# USB.net
KiCad netlist of a schematic drawn in Altium Designer
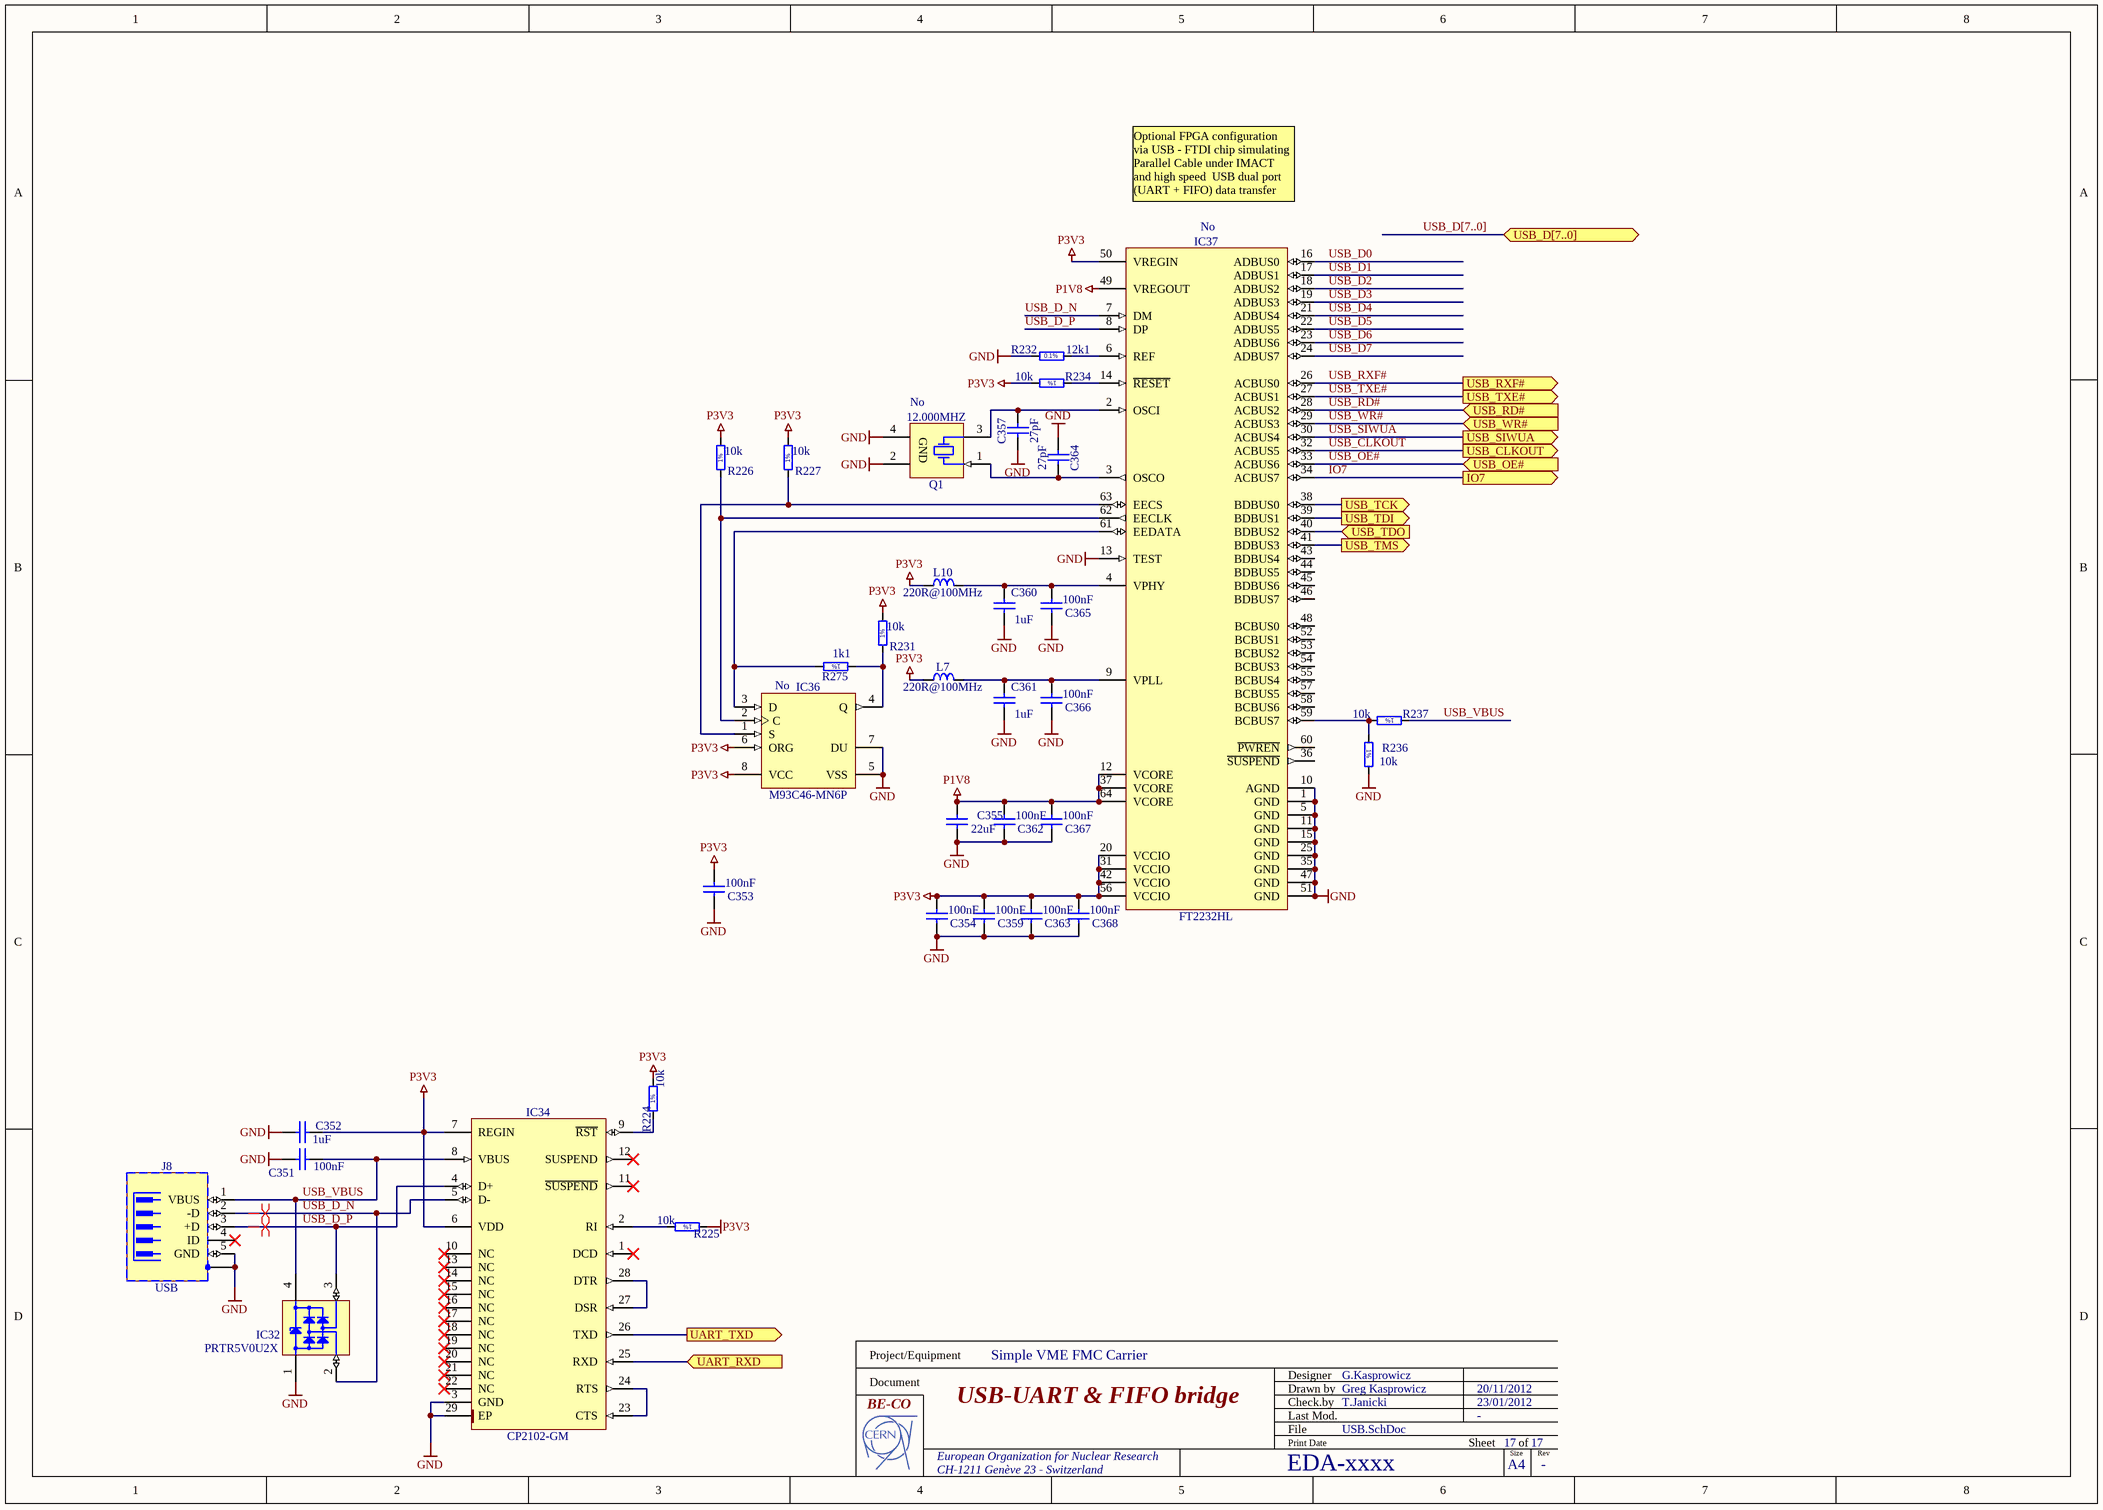
[diagram p0: USB.SchDoc]

(export (version "E")
  (design (tool "Eeschema 10.0.6"))
  (components
    (comp (ref "C351")
      (value "100nF")
      (footprint "CAPC1005X55N")
      (description "Non-polarised capacitor")
      (fields
        (field (name "PART NUMBER") "CC0402_100NF_16V_10%_X7R")
        (field (name "VOLTAGE") "16V")
        (field (name "AUTHOR") "CERN DEM JLC")
      )
      (libsource (lib "Capacitors") (part "Capacitor - non polarized"))
    )
    (comp (ref "C352")
      (value "1uF")
      (footprint "CAPC1608X87N")
      (description "Non-polarised capacitor")
      (fields
        (field (name "PART NUMBER") "CC0603_1UF_16V_10%_X7R")
        (field (name "VOLTAGE") "16V")
        (field (name "AUTHOR") "CERN DEM JLC")
      )
      (libsource (lib "Capacitors") (part "Capacitor - non polarized"))
    )
    (comp (ref "C353")
      (value "100nF")
      (footprint "CAPC1005X55N")
      (description "Non-polarised capacitor")
      (fields
        (field (name "PART NUMBER") "CC0402_100NF_16V_10%_X7R")
        (field (name "VOLTAGE") "16V")
        (field (name "AUTHOR") "CERN DEM JLC")
      )
      (libsource (lib "Capacitors") (part "Capacitor - non polarized"))
    )
    (comp (ref "C354")
      (value "100nF")
      (footprint "CAPC1005X55N")
      (description "Non-polarised capacitor")
      (fields
        (field (name "PART NUMBER") "CC0402_100NF_16V_10%_X7R")
        (field (name "VOLTAGE") "16V")
        (field (name "AUTHOR") "CERN DEM JLC")
      )
      (libsource (lib "Capacitors") (part "Capacitor - non polarized"))
    )
    (comp (ref "C355")
      (value "22uF")
      (footprint "CAPC3216X180N")
      (description "Non-polarised capacitor")
      (fields
        (field (name "PART NUMBER") "CC1206_22UF_10V_10%_X7R")
        (field (name "VOLTAGE") "10V")
        (field (name "AUTHOR") "CERN DEM JLC")
      )
      (libsource (lib "Capacitors") (part "Capacitor - non polarized"))
    )
    (comp (ref "C357")
      (value "27pF")
      (footprint "CAPC1608X87N")
      (description "Non-polarised capacitor")
      (fields
        (field (name "PART NUMBER") "CC0603_27PF_50V_5%_NP0")
        (field (name "VOLTAGE") "50V")
        (field (name "AUTHOR") "CERN DEM JLC")
      )
      (libsource (lib "Capacitors") (part "Capacitor - non polarized"))
    )
    (comp (ref "C359")
      (value "100nF")
      (footprint "CAPC1005X55N")
      (description "Non-polarised capacitor")
      (fields
        (field (name "PART NUMBER") "CC0402_100NF_16V_10%_X7R")
        (field (name "VOLTAGE") "16V")
        (field (name "AUTHOR") "CERN DEM JLC")
      )
      (libsource (lib "Capacitors") (part "Capacitor - non polarized"))
    )
    (comp (ref "C360")
      (value "1uF")
      (footprint "CAPC1608X87N")
      (description "Non-polarised capacitor")
      (fields
        (field (name "PART NUMBER") "CC0603_1UF_16V_10%_X7R")
        (field (name "VOLTAGE") "16V")
        (field (name "AUTHOR") "CERN DEM JLC")
      )
      (libsource (lib "Capacitors") (part "Capacitor - non polarized"))
    )
    (comp (ref "C361")
      (value "1uF")
      (footprint "CAPC1608X87N")
      (description "Non-polarised capacitor")
      (fields
        (field (name "PART NUMBER") "CC0603_1UF_16V_10%_X7R")
        (field (name "VOLTAGE") "16V")
        (field (name "AUTHOR") "CERN DEM JLC")
      )
      (libsource (lib "Capacitors") (part "Capacitor - non polarized"))
    )
    (comp (ref "C362")
      (value "100nF")
      (footprint "CAPC1005X55N")
      (description "Non-polarised capacitor")
      (fields
        (field (name "PART NUMBER") "CC0402_100NF_16V_10%_X7R")
        (field (name "VOLTAGE") "16V")
        (field (name "AUTHOR") "CERN DEM JLC")
      )
      (libsource (lib "Capacitors") (part "Capacitor - non polarized"))
    )
    (comp (ref "C363")
      (value "100nF")
      (footprint "CAPC1005X55N")
      (description "Non-polarised capacitor")
      (fields
        (field (name "PART NUMBER") "CC0402_100NF_16V_10%_X7R")
        (field (name "VOLTAGE") "16V")
        (field (name "AUTHOR") "CERN DEM JLC")
      )
      (libsource (lib "Capacitors") (part "Capacitor - non polarized"))
    )
    (comp (ref "C364")
      (value "27pF")
      (footprint "CAPC1608X87N")
      (description "Non-polarised capacitor")
      (fields
        (field (name "PART NUMBER") "CC0603_27PF_50V_5%_NP0")
        (field (name "VOLTAGE") "50V")
        (field (name "AUTHOR") "CERN DEM JLC")
      )
      (libsource (lib "Capacitors") (part "Capacitor - non polarized"))
    )
    (comp (ref "C365")
      (value "100nF")
      (footprint "CAPC1005X55N")
      (description "Non-polarised capacitor")
      (fields
        (field (name "PART NUMBER") "CC0402_100NF_16V_10%_X7R")
        (field (name "VOLTAGE") "16V")
        (field (name "AUTHOR") "CERN DEM JLC")
      )
      (libsource (lib "Capacitors") (part "Capacitor - non polarized"))
    )
    (comp (ref "C366")
      (value "100nF")
      (footprint "CAPC1005X55N")
      (description "Non-polarised capacitor")
      (fields
        (field (name "PART NUMBER") "CC0402_100NF_16V_10%_X7R")
        (field (name "VOLTAGE") "16V")
        (field (name "AUTHOR") "CERN DEM JLC")
      )
      (libsource (lib "Capacitors") (part "Capacitor - non polarized"))
    )
    (comp (ref "C367")
      (value "100nF")
      (footprint "CAPC1005X55N")
      (description "Non-polarised capacitor")
      (fields
        (field (name "PART NUMBER") "CC0402_100NF_16V_10%_X7R")
        (field (name "VOLTAGE") "16V")
        (field (name "AUTHOR") "CERN DEM JLC")
      )
      (libsource (lib "Capacitors") (part "Capacitor - non polarized"))
    )
    (comp (ref "C368")
      (value "100nF")
      (footprint "CAPC1005X55N")
      (description "Non-polarised capacitor")
      (fields
        (field (name "PART NUMBER") "CC0402_100NF_16V_10%_X7R")
        (field (name "VOLTAGE") "16V")
        (field (name "AUTHOR") "CERN DEM JLC")
      )
      (libsource (lib "Capacitors") (part "Capacitor - non polarized"))
    )
    (comp (ref "IC32")
      (value "PRTR5V0U2X")
      (footprint "SOT190P230X110-4N")
      (description "Ultra Low Capacitance Double Rail-to-Rail ESD Protection Diode")
      (fields
        (field (name "VOLTAGE") "5.5V")
        (field (name "MANUFACTURER") "PHILIPS NXP")
        (field (name "AUTHOR") "CERN DEM JLC")
      )
      (libsource (lib "ICs And Semiconductors") (part "PRTR5V0U2X"))
    )
    (comp (ref "IC34")
      (value "CP2102-GM")
      (footprint "QFN50P500X500X100-29N-S335")
      (description "Single-Chip USB to UART Bridge")
      (fields (field (name "MANUFACTURER") "SILICON LABS") (field (name "AUTHOR") "CERN DEM JLC"))
      (libsource (lib "ICs And Semiconductors") (part "CP2102-GM"))
    )
    (comp (ref "IC36")
      (value "M93C46-MN6P")
      (footprint "SOIC127P600X175-8N")
      (description "1Kb (x8/x16) Serial Microwire Bus EEPROM")
      (fields
        (field (name "MANUFACTURER") "ST MICROELECTRONICS")
        (field (name "MOUNTED") "No")
        (field (name "AUTHOR") "CERN DEM JLC")
      )
      (libsource (lib "ICs And Semiconductors") (part "M93C46-MN"))
    )
    (comp (ref "IC37")
      (value "FT2232HL")
      (footprint "QFP50P1200X1200X160-64N")
      (description "Dual High Speed USB to Multipurpose UART/FIFO IC")
      (fields
        (field (name "MANUFACTURER") "FUTURE TECHNOLOGY DEVICES INTERNATIONAL (FTDI)")
        (field (name "MOUNTED") "No")
        (field (name "AUTHOR") "CERN DEM JLC")
      )
      (libsource (lib "ICs And Semiconductors") (part "FT2232H"))
    )
    (comp (ref "J8")
      (value "USB")
      (footprint "TYCO_1734035-1")
      (description "5 Pin + 1 Shield USB Receptacle")
      (fields
        (field (name "PART NUMBER") "TYCO_1734035-1")
        (field (name "MANUFACTURER") "TYCO ELECTRONICS")
        (field (name "AUTHOR") "CERN DEM JLC")
      )
      (libsource (lib "Connectors") (part "Connector USB 5 Pin + 1Shield"))
    )
    (comp (ref "L7")
      (value "220R@100MHz")
      (footprint "INDC2012X105N")
      (description "Inductor")
      (fields
        (field (name "PART NUMBER") "IND0805_MURATA_BLM21PG221SN1D")
        (field (name "POWER") "2A")
        (field (name "AUTHOR") "CERN DEM JLC")
      )
      (libsource (lib "Inductors & Transformers") (part "Inductor"))
    )
    (comp (ref "L10")
      (value "220R@100MHz")
      (footprint "INDC2012X105N")
      (description "Inductor")
      (fields
        (field (name "PART NUMBER") "IND0805_MURATA_BLM21PG221SN1D")
        (field (name "POWER") "2A")
        (field (name "AUTHOR") "CERN DEM JLC")
      )
      (libsource (lib "Inductors & Transformers") (part "Inductor"))
    )
    (comp (ref "Q1")
      (value "12.000MHZ")
      (footprint "XTAL_ABRACON_ABM3B")
      (description "Crystal 4 pins 1=XTAL Control 2=GND3=XTAL 4=GND")
      (fields
        (field (name "PART NUMBER") "XTAL_12.000MHZ_ABRACON_ABM3B-12.000MHZ-B2-T")
        (field (name "MANUFACTURER") "ABRACON")
        (field (name "MOUNTED") "No")
        (field (name "AUTHOR") "CERN DEM JLC")
      )
      (libsource (lib "ICs And Semiconductors") (part "Quartz Crystal 1X 2GND 3X 4GND"))
    )
    (comp (ref "R224")
      (value "10k")
      (footprint "RESC1608X55N")
      (description "Resistor - 1%")
      (fields
        (field (name "PART NUMBER") "R0603_10K_1%_0.1W_100PPM")
        (field (name "POWER") "0.1W")
        (field (name "AUTHOR") "CERN DEM JLC")
      )
      (libsource (lib "Resistors") (part "Resistor - 1%"))
    )
    (comp (ref "R225")
      (value "10k")
      (footprint "RESC1608X55N")
      (description "Resistor - 1%")
      (fields
        (field (name "PART NUMBER") "R0603_10K_1%_0.1W_100PPM")
        (field (name "POWER") "0.1W")
        (field (name "AUTHOR") "CERN DEM JLC")
      )
      (libsource (lib "Resistors") (part "Resistor - 1%"))
    )
    (comp (ref "R226")
      (value "10k")
      (footprint "RESC1608X55N")
      (description "Resistor - 1%")
      (fields
        (field (name "PART NUMBER") "R0603_10K_1%_0.1W_100PPM")
        (field (name "POWER") "0.1W")
        (field (name "AUTHOR") "CERN DEM JLC")
      )
      (libsource (lib "Resistors") (part "Resistor - 1%"))
    )
    (comp (ref "R227")
      (value "10k")
      (footprint "RESC1608X55N")
      (description "Resistor - 1%")
      (fields
        (field (name "PART NUMBER") "R0603_10K_1%_0.1W_100PPM")
        (field (name "POWER") "0.1W")
        (field (name "AUTHOR") "CERN DEM JLC")
      )
      (libsource (lib "Resistors") (part "Resistor - 1%"))
    )
    (comp (ref "R231")
      (value "10k")
      (footprint "RESC1608X55N")
      (description "Resistor - 1%")
      (fields
        (field (name "PART NUMBER") "R0603_10K_1%_0.1W_100PPM")
        (field (name "POWER") "0.1W")
        (field (name "AUTHOR") "CERN DEM JLC")
      )
      (libsource (lib "Resistors") (part "Resistor - 1%"))
    )
    (comp (ref "R232")
      (value "12k1")
      (footprint "RESC1608X55N")
      (description "Resistor - 0.1%")
      (fields
        (field (name "PART NUMBER") "R0603_12K1_0.1%_0.063W_10PPM")
        (field (name "POWER") "0.063W")
        (field (name "AUTHOR") "CERN DEM JLC")
      )
      (libsource (lib "Resistors") (part "Resistor - 0.1%"))
    )
    (comp (ref "R234")
      (value "10k")
      (footprint "RESC1608X55N")
      (description "Resistor - 1%")
      (fields
        (field (name "PART NUMBER") "R0603_10K_1%_0.1W_100PPM")
        (field (name "POWER") "0.1W")
        (field (name "AUTHOR") "CERN DEM JLC")
      )
      (libsource (lib "Resistors") (part "Resistor - 1%"))
    )
    (comp (ref "R236")
      (value "10k")
      (footprint "RESC1608X55N")
      (description "Resistor - 1%")
      (fields
        (field (name "PART NUMBER") "R0603_10K_1%_0.1W_100PPM")
        (field (name "POWER") "0.1W")
        (field (name "AUTHOR") "CERN DEM JLC")
      )
      (libsource (lib "Resistors") (part "Resistor - 1%"))
    )
    (comp (ref "R237")
      (value "10k")
      (footprint "RESC1608X55N")
      (description "Resistor - 1%")
      (fields
        (field (name "PART NUMBER") "R0603_10K_1%_0.1W_100PPM")
        (field (name "POWER") "0.1W")
        (field (name "AUTHOR") "CERN DEM JLC")
      )
      (libsource (lib "Resistors") (part "Resistor - 1%"))
    )
    (comp (ref "R275")
      (value "1k1")
      (footprint "RESC1608X55N")
      (description "Resistor - 1%")
      (fields
        (field (name "PART NUMBER") "R0603_1K1_1%_0.1W_100PPM")
        (field (name "POWER") "0.1W")
        (field (name "AUTHOR") "CERN DEM JLC")
      )
      (libsource (lib "Resistors") (part "Resistor - 1%"))
    )
  )
  (nets
    (net (code "1") (name "/IO7") (class "Default")
      (node (ref "IC37") (pin "34") (pinfunction "ACBUS7_34") (pintype "bidirectional"))
    )
    (net (code "2") (name "/UART_RXD") (class "Default")
      (node (ref "IC34") (pin "25") (pinfunction "RXD_25") (pintype "input"))
    )
    (net (code "3") (name "/UART_TXD") (class "Default")
      (node (ref "IC34") (pin "26") (pinfunction "TXD_26") (pintype "output"))
    )
    (net (code "4") (name "/USB_CLKOUT") (class "Default")
      (node (ref "IC37") (pin "32") (pinfunction "ACBUS5_32") (pintype "bidirectional"))
    )
    (net (code "5") (name "/USB_D0") (class "Default")
      (node (ref "IC37") (pin "16") (pinfunction "ADBUS0_16") (pintype "bidirectional"))
    )
    (net (code "6") (name "/USB_D1") (class "Default")
      (node (ref "IC37") (pin "17") (pinfunction "ADBUS1_17") (pintype "bidirectional"))
    )
    (net (code "7") (name "/USB_D2") (class "Default")
      (node (ref "IC37") (pin "18") (pinfunction "ADBUS2_18") (pintype "bidirectional"))
    )
    (net (code "8") (name "/USB_D3") (class "Default")
      (node (ref "IC37") (pin "19") (pinfunction "ADBUS3_19") (pintype "bidirectional"))
    )
    (net (code "9") (name "/USB_D4") (class "Default")
      (node (ref "IC37") (pin "21") (pinfunction "ADBUS4_21") (pintype "bidirectional"))
    )
    (net (code "10") (name "/USB_D5") (class "Default")
      (node (ref "IC37") (pin "22") (pinfunction "ADBUS5_22") (pintype "bidirectional"))
    )
    (net (code "11") (name "/USB_D6") (class "Default")
      (node (ref "IC37") (pin "23") (pinfunction "ADBUS6_23") (pintype "bidirectional"))
    )
    (net (code "12") (name "/USB_D7") (class "Default")
      (node (ref "IC37") (pin "24") (pinfunction "ADBUS7_24") (pintype "bidirectional"))
    )
    (net (code "14") (name "/USB_D_N") (class "Default")
      (node (ref "IC32") (pin "2") (pinfunction "I/O1_2") (pintype "bidirectional"))
      (node (ref "IC34") (pin "5") (pinfunction "D-_5") (pintype "bidirectional"))
      (node (ref "IC37") (pin "7") (pinfunction "DM_7") (pintype "input"))
      (node (ref "J8") (pin "2") (pinfunction "-D_2") (pintype "bidirectional"))
    )
    (net (code "15") (name "/USB_D_P") (class "Default")
      (node (ref "IC32") (pin "3") (pinfunction "I/O2_3") (pintype "bidirectional"))
      (node (ref "IC34") (pin "4") (pinfunction "D+_4") (pintype "bidirectional"))
      (node (ref "IC37") (pin "8") (pinfunction "DP_8") (pintype "input"))
      (node (ref "J8") (pin "3") (pinfunction "+D_3") (pintype "bidirectional"))
    )
    (net (code "16") (name "/USB_OE#") (class "Default")
      (node (ref "IC37") (pin "33") (pinfunction "ACBUS6_33") (pintype "bidirectional"))
    )
    (net (code "17") (name "/USB_RD#") (class "Default")
      (node (ref "IC37") (pin "28") (pinfunction "ACBUS2_28") (pintype "bidirectional"))
    )
    (net (code "18") (name "/USB_RXF#") (class "Default")
      (node (ref "IC37") (pin "26") (pinfunction "ACBUS0_26") (pintype "bidirectional"))
    )
    (net (code "19") (name "/USB_SIWUA") (class "Default")
      (node (ref "IC37") (pin "30") (pinfunction "ACBUS4_30") (pintype "bidirectional"))
    )
    (net (code "20") (name "/USB_TCK") (class "Default")
      (node (ref "IC37") (pin "38") (pinfunction "BDBUS0_38") (pintype "bidirectional"))
    )
    (net (code "21") (name "/USB_TDI") (class "Default")
      (node (ref "IC37") (pin "39") (pinfunction "BDBUS1_39") (pintype "bidirectional"))
    )
    (net (code "22") (name "/USB_TDO") (class "Default")
      (node (ref "IC37") (pin "40") (pinfunction "BDBUS2_40") (pintype "bidirectional"))
    )
    (net (code "23") (name "/USB_TMS") (class "Default")
      (node (ref "IC37") (pin "41") (pinfunction "BDBUS3_41") (pintype "bidirectional"))
    )
    (net (code "24") (name "/USB_TXE#") (class "Default")
      (node (ref "IC37") (pin "27") (pinfunction "ACBUS1_27") (pintype "bidirectional"))
    )
    (net (code "25") (name "/USB_VBUS") (class "Default")
      (node (ref "C351") (pin "1") (pinfunction "1_1") (pintype "passive"))
      (node (ref "IC32") (pin "4") (pinfunction "VCC_4") (pintype "power_in"))
      (node (ref "IC34") (pin "8") (pinfunction "VBUS_8") (pintype "input"))
      (node (ref "J8") (pin "1") (pinfunction "VBUS_1") (pintype "bidirectional"))
      (node (ref "R237") (pin "1") (pinfunction "1_1") (pintype "passive"))
    )
    (net (code "26") (name "/USB_WR#") (class "Default")
      (node (ref "IC37") (pin "29") (pinfunction "ACBUS3_29") (pintype "bidirectional"))
    )
    (net (code "27") (name "GND") (class "Default")
      (node (ref "C351") (pin "2") (pinfunction "2_2") (pintype "passive"))
      (node (ref "C352") (pin "2") (pinfunction "2_2") (pintype "passive"))
      (node (ref "C353") (pin "2") (pinfunction "2_2") (pintype "passive"))
      (node (ref "C354") (pin "2") (pinfunction "2_2") (pintype "passive"))
      (node (ref "C355") (pin "1") (pinfunction "1_1") (pintype "passive"))
      (node (ref "C357") (pin "1") (pinfunction "1_1") (pintype "passive"))
      (node (ref "C359") (pin "2") (pinfunction "2_2") (pintype "passive"))
      (node (ref "C360") (pin "1") (pinfunction "1_1") (pintype "passive"))
      (node (ref "C361") (pin "1") (pinfunction "1_1") (pintype "passive"))
      (node (ref "C362") (pin "2") (pinfunction "2_2") (pintype "passive"))
      (node (ref "C363") (pin "2") (pinfunction "2_2") (pintype "passive"))
      (node (ref "C364") (pin "1") (pinfunction "1_1") (pintype "passive"))
      (node (ref "C365") (pin "2") (pinfunction "2_2") (pintype "passive"))
      (node (ref "C366") (pin "2") (pinfunction "2_2") (pintype "passive"))
      (node (ref "C367") (pin "2") (pinfunction "2_2") (pintype "passive"))
      (node (ref "C368") (pin "2") (pinfunction "2_2") (pintype "passive"))
      (node (ref "IC32") (pin "1") (pinfunction "GND_1") (pintype "power_in"))
      (node (ref "IC34") (pin "29") (pinfunction "EP_29") (pintype "power_in"))
      (node (ref "IC34") (pin "3") (pinfunction "GND_3") (pintype "power_in"))
      (node (ref "IC36") (pin "5") (pinfunction "VSS_5") (pintype "power_in"))
      (node (ref "IC36") (pin "7") (pinfunction "DU_7") (pintype "passive"))
      (node (ref "IC37") (pin "1") (pinfunction "GND_1") (pintype "power_in"))
      (node (ref "IC37") (pin "10") (pinfunction "AGND_10") (pintype "power_in"))
      (node (ref "IC37") (pin "11") (pinfunction "GND_11") (pintype "power_in"))
      (node (ref "IC37") (pin "13") (pinfunction "TEST_13") (pintype "input"))
      (node (ref "IC37") (pin "15") (pinfunction "GND_15") (pintype "power_in"))
      (node (ref "IC37") (pin "25") (pinfunction "GND_25") (pintype "power_in"))
      (node (ref "IC37") (pin "35") (pinfunction "GND_35") (pintype "power_in"))
      (node (ref "IC37") (pin "47") (pinfunction "GND_47") (pintype "power_in"))
      (node (ref "IC37") (pin "5") (pinfunction "GND_5") (pintype "power_in"))
      (node (ref "IC37") (pin "51") (pinfunction "GND_51") (pintype "power_in"))
      (node (ref "J8") (pin "5") (pinfunction "GND_5") (pintype "bidirectional"))
      (node (ref "J8") (pin "6") (pinfunction "SH_6") (pintype "power_in"))
      (node (ref "Q1") (pin "2") (pinfunction "GND_2") (pintype "power_in"))
      (node (ref "Q1") (pin "4") (pinfunction "GND_4") (pintype "power_in"))
      (node (ref "R232") (pin "1") (pinfunction "1_1") (pintype "passive"))
      (node (ref "R236") (pin "2") (pinfunction "2_2") (pintype "passive"))
    )
    (net (code "28") (name "Net-(IC34-CTS)") (class "Default")
      (node (ref "IC34") (pin "23") (pinfunction "CTS_23") (pintype "input"))
      (node (ref "IC34") (pin "24") (pinfunction "RTS_24") (pintype "output"))
    )
    (net (code "29") (name "Net-(IC34-DSR)") (class "Default")
      (node (ref "IC34") (pin "27") (pinfunction "DSR_27") (pintype "input"))
      (node (ref "IC34") (pin "28") (pinfunction "DTR_28") (pintype "output"))
    )
    (net (code "30") (name "Net-(IC34-RI)") (class "Default")
      (node (ref "IC34") (pin "2") (pinfunction "RI_2") (pintype "input"))
      (node (ref "R225") (pin "2") (pinfunction "2_2") (pintype "passive"))
    )
    (net (code "31") (name "Net-(IC34-~{RST})") (class "Default")
      (node (ref "IC34") (pin "9") (pinfunction "~{RST}_9") (pintype "bidirectional"))
      (node (ref "R224") (pin "1") (pinfunction "1_1") (pintype "passive"))
    )
    (net (code "32") (name "Net-(IC36-C)") (class "Default")
      (node (ref "IC36") (pin "2") (pinfunction "C_2") (pintype "input"))
      (node (ref "IC37") (pin "62") (pinfunction "EECLK_62") (pintype "output"))
      (node (ref "R226") (pin "1") (pinfunction "1_1") (pintype "passive"))
    )
    (net (code "33") (name "Net-(IC36-D)") (class "Default")
      (node (ref "IC36") (pin "3") (pinfunction "D_3") (pintype "input"))
      (node (ref "IC37") (pin "61") (pinfunction "EEDATA_61") (pintype "bidirectional"))
      (node (ref "R275") (pin "2") (pinfunction "2_2") (pintype "passive"))
    )
    (net (code "34") (name "Net-(IC36-Q)") (class "Default")
      (node (ref "IC36") (pin "4") (pinfunction "Q_4") (pintype "output"))
      (node (ref "R231") (pin "1") (pinfunction "1_1") (pintype "passive"))
      (node (ref "R275") (pin "1") (pinfunction "1_1") (pintype "passive"))
    )
    (net (code "35") (name "Net-(IC36-S)") (class "Default")
      (node (ref "IC36") (pin "1") (pinfunction "S_1") (pintype "input"))
      (node (ref "IC37") (pin "63") (pinfunction "EECS_63") (pintype "bidirectional"))
      (node (ref "R227") (pin "1") (pinfunction "1_1") (pintype "passive"))
    )
    (net (code "36") (name "Net-(IC37-BCBUS7)") (class "Default")
      (node (ref "IC37") (pin "59") (pinfunction "BCBUS7_59") (pintype "bidirectional"))
      (node (ref "R236") (pin "1") (pinfunction "1_1") (pintype "passive"))
      (node (ref "R237") (pin "2") (pinfunction "2_2") (pintype "passive"))
    )
    (net (code "37") (name "Net-(IC37-OSCI)") (class "Default")
      (node (ref "C357") (pin "2") (pinfunction "2_2") (pintype "passive"))
      (node (ref "IC37") (pin "2") (pinfunction "OSCI_2") (pintype "input"))
      (node (ref "Q1") (pin "3") (pinfunction "X_3") (pintype "power_in"))
    )
    (net (code "38") (name "Net-(IC37-OSCO)") (class "Default")
      (node (ref "C364") (pin "2") (pinfunction "2_2") (pintype "passive"))
      (node (ref "IC37") (pin "3") (pinfunction "OSCO_3") (pintype "output"))
      (node (ref "Q1") (pin "1") (pinfunction "X_1") (pintype "input"))
    )
    (net (code "39") (name "Net-(IC37-REF)") (class "Default")
      (node (ref "IC37") (pin "6") (pinfunction "REF_6") (pintype "input"))
      (node (ref "R232") (pin "2") (pinfunction "2_2") (pintype "passive"))
    )
    (net (code "40") (name "Net-(IC37-VPHY)") (class "Default")
      (node (ref "C360") (pin "2") (pinfunction "2_2") (pintype "passive"))
      (node (ref "C365") (pin "1") (pinfunction "1_1") (pintype "passive"))
      (node (ref "IC37") (pin "4") (pinfunction "VPHY_4") (pintype "power_in"))
      (node (ref "L10") (pin "2") (pinfunction "2_2") (pintype "passive"))
    )
    (net (code "41") (name "Net-(IC37-VPLL)") (class "Default")
      (node (ref "C361") (pin "2") (pinfunction "2_2") (pintype "passive"))
      (node (ref "C366") (pin "1") (pinfunction "1_1") (pintype "passive"))
      (node (ref "IC37") (pin "9") (pinfunction "VPLL_9") (pintype "power_in"))
      (node (ref "L7") (pin "2") (pinfunction "2_2") (pintype "passive"))
    )
    (net (code "42") (name "Net-(IC37-~{RESET})") (class "Default")
      (node (ref "IC37") (pin "14") (pinfunction "~{RESET}_14") (pintype "input"))
      (node (ref "R234") (pin "1") (pinfunction "1_1") (pintype "passive"))
    )
    (net (code "43") (name "P1V8") (class "Default")
      (node (ref "C355") (pin "2") (pinfunction "2_2") (pintype "passive"))
      (node (ref "C362") (pin "1") (pinfunction "1_1") (pintype "passive"))
      (node (ref "C367") (pin "1") (pinfunction "1_1") (pintype "passive"))
      (node (ref "IC37") (pin "12") (pinfunction "VCORE_12") (pintype "power_in"))
      (node (ref "IC37") (pin "37") (pinfunction "VCORE_37") (pintype "power_in"))
      (node (ref "IC37") (pin "49") (pinfunction "VREGOUT_49") (pintype "power_in"))
      (node (ref "IC37") (pin "64") (pinfunction "VCORE_64") (pintype "power_in"))
    )
    (net (code "44") (name "P3V3") (class "Default")
      (node (ref "C352") (pin "1") (pinfunction "1_1") (pintype "passive"))
      (node (ref "C353") (pin "1") (pinfunction "1_1") (pintype "passive"))
      (node (ref "C354") (pin "1") (pinfunction "1_1") (pintype "passive"))
      (node (ref "C359") (pin "1") (pinfunction "1_1") (pintype "passive"))
      (node (ref "C363") (pin "1") (pinfunction "1_1") (pintype "passive"))
      (node (ref "C368") (pin "1") (pinfunction "1_1") (pintype "passive"))
      (node (ref "IC34") (pin "6") (pinfunction "VDD_6") (pintype "power_in"))
      (node (ref "IC34") (pin "7") (pinfunction "REGIN_7") (pintype "power_in"))
      (node (ref "IC36") (pin "6") (pinfunction "ORG_6") (pintype "input"))
      (node (ref "IC36") (pin "8") (pinfunction "VCC_8") (pintype "power_in"))
      (node (ref "IC37") (pin "20") (pinfunction "VCCIO_20") (pintype "power_in"))
      (node (ref "IC37") (pin "31") (pinfunction "VCCIO_31") (pintype "power_in"))
      (node (ref "IC37") (pin "42") (pinfunction "VCCIO_42") (pintype "power_in"))
      (node (ref "IC37") (pin "50") (pinfunction "VREGIN_50") (pintype "power_in"))
      (node (ref "IC37") (pin "56") (pinfunction "VCCIO_56") (pintype "power_in"))
      (node (ref "L10") (pin "1") (pinfunction "1_1") (pintype "passive"))
      (node (ref "L7") (pin "1") (pinfunction "1_1") (pintype "passive"))
      (node (ref "R224") (pin "2") (pinfunction "2_2") (pintype "passive"))
      (node (ref "R225") (pin "1") (pinfunction "1_1") (pintype "passive"))
      (node (ref "R226") (pin "2") (pinfunction "2_2") (pintype "passive"))
      (node (ref "R227") (pin "2") (pinfunction "2_2") (pintype "passive"))
      (node (ref "R231") (pin "2") (pinfunction "2_2") (pintype "passive"))
      (node (ref "R234") (pin "2") (pinfunction "2_2") (pintype "passive"))
    )
    (net (code "45") (name "unconnected-(IC34-DCD-Pad1)") (class "Default")
      (node (ref "IC34") (pin "1") (pinfunction "DCD_1") (pintype "input+no_connect"))
    )
    (net (code "46") (name "unconnected-(IC34-NC-Pad10)") (class "Default")
      (node (ref "IC34") (pin "10") (pinfunction "NC_10") (pintype "passive+no_connect"))
    )
    (net (code "47") (name "unconnected-(IC34-NC-Pad13)") (class "Default")
      (node (ref "IC34") (pin "13") (pinfunction "NC_13") (pintype "passive+no_connect"))
    )
    (net (code "48") (name "unconnected-(IC34-NC-Pad14)") (class "Default")
      (node (ref "IC34") (pin "14") (pinfunction "NC_14") (pintype "passive+no_connect"))
    )
    (net (code "49") (name "unconnected-(IC34-NC-Pad15)") (class "Default")
      (node (ref "IC34") (pin "15") (pinfunction "NC_15") (pintype "passive+no_connect"))
    )
    (net (code "50") (name "unconnected-(IC34-NC-Pad16)") (class "Default")
      (node (ref "IC34") (pin "16") (pinfunction "NC_16") (pintype "passive+no_connect"))
    )
    (net (code "51") (name "unconnected-(IC34-NC-Pad17)") (class "Default")
      (node (ref "IC34") (pin "17") (pinfunction "NC_17") (pintype "passive+no_connect"))
    )
    (net (code "52") (name "unconnected-(IC34-NC-Pad18)") (class "Default")
      (node (ref "IC34") (pin "18") (pinfunction "NC_18") (pintype "passive+no_connect"))
    )
    (net (code "53") (name "unconnected-(IC34-NC-Pad19)") (class "Default")
      (node (ref "IC34") (pin "19") (pinfunction "NC_19") (pintype "passive+no_connect"))
    )
    (net (code "54") (name "unconnected-(IC34-NC-Pad20)") (class "Default")
      (node (ref "IC34") (pin "20") (pinfunction "NC_20") (pintype "passive+no_connect"))
    )
    (net (code "55") (name "unconnected-(IC34-NC-Pad21)") (class "Default")
      (node (ref "IC34") (pin "21") (pinfunction "NC_21") (pintype "passive+no_connect"))
    )
    (net (code "56") (name "unconnected-(IC34-NC-Pad22)") (class "Default")
      (node (ref "IC34") (pin "22") (pinfunction "NC_22") (pintype "passive+no_connect"))
    )
    (net (code "57") (name "unconnected-(IC34-SUSPEND-Pad12)") (class "Default")
      (node (ref "IC34") (pin "12") (pinfunction "SUSPEND_12") (pintype "output+no_connect"))
    )
    (net (code "58") (name "unconnected-(IC34-~{SUSPEND}-Pad11)") (class "Default")
      (node (ref "IC34") (pin "11") (pinfunction "~{SUSPEND}_11") (pintype "output+no_connect"))
    )
    (net (code "59") (name "unconnected-(IC37-BCBUS0-Pad48)") (class "Default")
      (node (ref "IC37") (pin "48") (pinfunction "BCBUS0_48") (pintype "bidirectional"))
    )
    (net (code "60") (name "unconnected-(IC37-BCBUS1-Pad52)") (class "Default")
      (node (ref "IC37") (pin "52") (pinfunction "BCBUS1_52") (pintype "bidirectional"))
    )
    (net (code "61") (name "unconnected-(IC37-BCBUS2-Pad53)") (class "Default")
      (node (ref "IC37") (pin "53") (pinfunction "BCBUS2_53") (pintype "bidirectional"))
    )
    (net (code "62") (name "unconnected-(IC37-BCBUS3-Pad54)") (class "Default")
      (node (ref "IC37") (pin "54") (pinfunction "BCBUS3_54") (pintype "bidirectional"))
    )
    (net (code "63") (name "unconnected-(IC37-BCBUS4-Pad55)") (class "Default")
      (node (ref "IC37") (pin "55") (pinfunction "BCBUS4_55") (pintype "bidirectional"))
    )
    (net (code "64") (name "unconnected-(IC37-BCBUS5-Pad57)") (class "Default")
      (node (ref "IC37") (pin "57") (pinfunction "BCBUS5_57") (pintype "bidirectional"))
    )
    (net (code "65") (name "unconnected-(IC37-BCBUS6-Pad58)") (class "Default")
      (node (ref "IC37") (pin "58") (pinfunction "BCBUS6_58") (pintype "bidirectional"))
    )
    (net (code "66") (name "unconnected-(IC37-BDBUS4-Pad43)") (class "Default")
      (node (ref "IC37") (pin "43") (pinfunction "BDBUS4_43") (pintype "bidirectional"))
    )
    (net (code "67") (name "unconnected-(IC37-BDBUS5-Pad44)") (class "Default")
      (node (ref "IC37") (pin "44") (pinfunction "BDBUS5_44") (pintype "bidirectional"))
    )
    (net (code "68") (name "unconnected-(IC37-BDBUS6-Pad45)") (class "Default")
      (node (ref "IC37") (pin "45") (pinfunction "BDBUS6_45") (pintype "bidirectional"))
    )
    (net (code "69") (name "unconnected-(IC37-BDBUS7-Pad46)") (class "Default")
      (node (ref "IC37") (pin "46") (pinfunction "BDBUS7_46") (pintype "bidirectional"))
    )
    (net (code "70") (name "unconnected-(IC37-~{PWREN}-Pad60)") (class "Default")
      (node (ref "IC37") (pin "60") (pinfunction "~{PWREN}_60") (pintype "output"))
    )
    (net (code "71") (name "unconnected-(IC37-~{SUSPEND}-Pad36)") (class "Default")
      (node (ref "IC37") (pin "36") (pinfunction "~{SUSPEND}_36") (pintype "output"))
    )
    (net (code "72") (name "unconnected-(J8-ID-Pad4)") (class "Default")
      (node (ref "J8") (pin "4") (pinfunction "ID_4") (pintype "passive+no_connect"))
    )
  )
)
